# robotShield_Schematic.net
KiCad netlist of a schematic drawn in Altium Designer
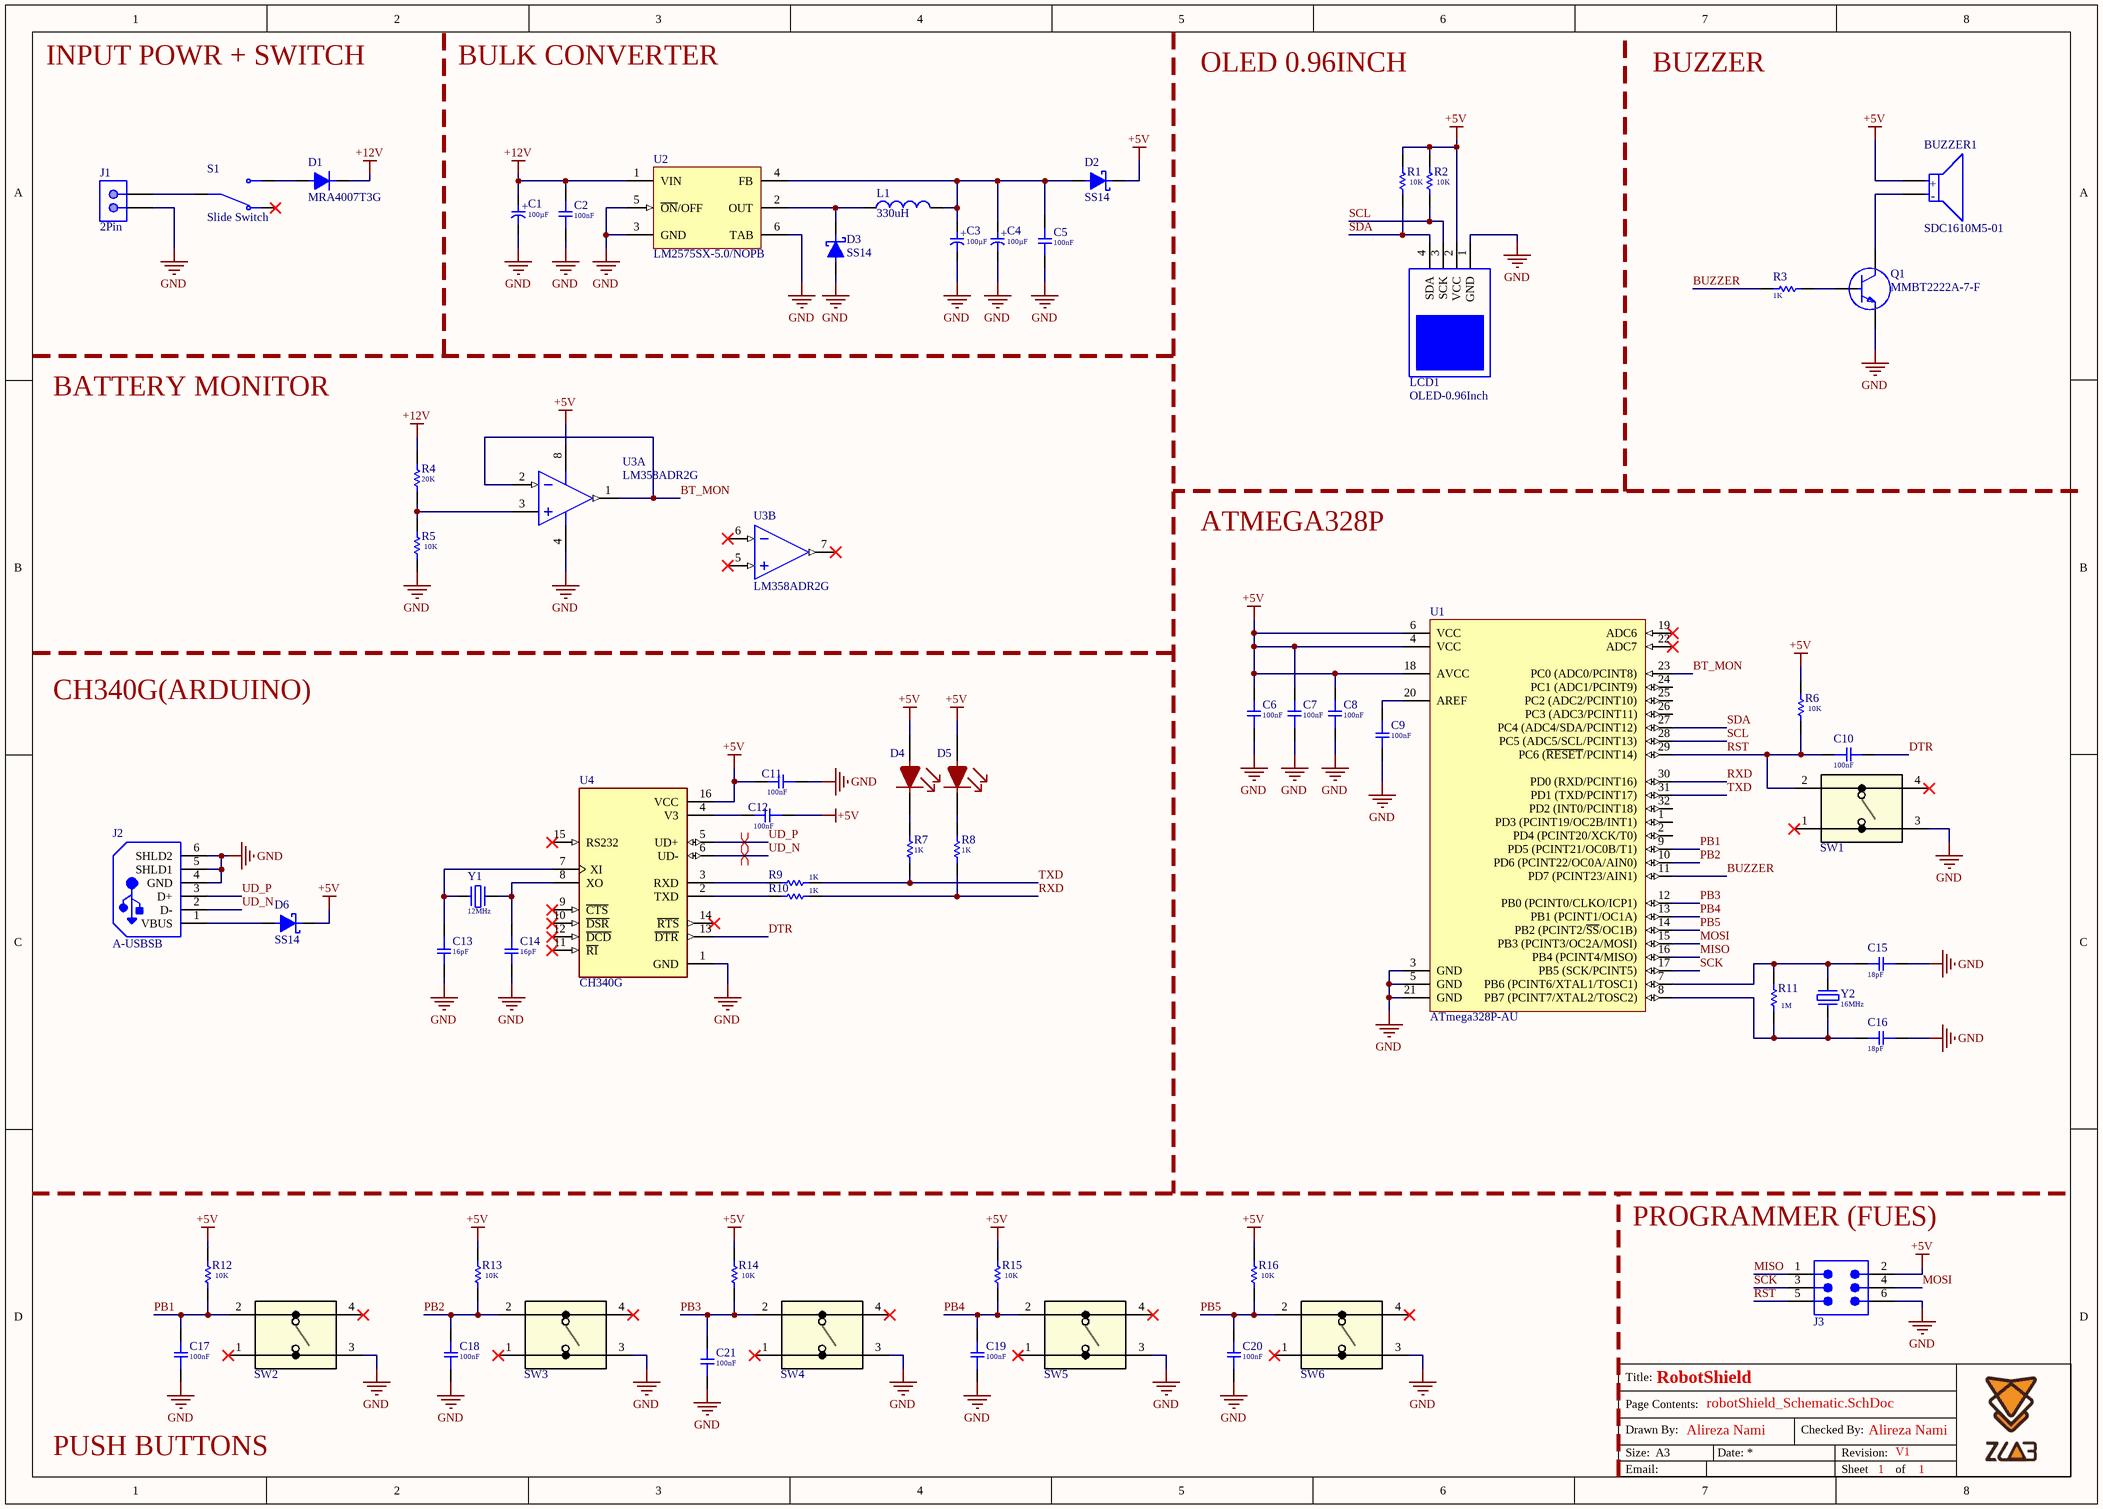
[diagram p0: robotShield_Schematic.SchDoc]

(export (version "E")
  (design (tool "Eeschema 10.0.6"))
  (components
    (comp (ref "BUZZER1")
      (value "SDC1610M5-01")
      (footprint "BUZZER")
      (description "AUDIO MAGNETIC INDICATOR 4-8V TH")
      (libsource (lib "robotShiedl") (part "BUZZER-5V"))
    )
    (comp (ref "C1")
      (value "MAL215376101E3")
      (footprint "CE-8x10mm")
      (description "MAL215376101E3 Cap Aluminum 100uF 25V 20% (8 X 10mm) SMD 0.5 Ohm 180mA 3000h 105C Blister T/R")
      (fields
        (field (name "VOLTAGE") "25V")
        (field (name "TOLERANCE") "20%")
        (field (name "CAPACITANCE") "100µF")
      )
      (libsource (lib "robotShiedl") (part "CE-100uF-25V"))
    )
    (comp (ref "C2")
      (value "CGA3E2X7R1H104K080AA")
      (footprint "C0603")
      (description "Cap Ceramic 100nF 50V X7R 10% Pad SMD 0603 +125°C Automotive T/R")
      (fields
        (field (name "TOLERANCE") "10%")
        (field (name "CAPACITANCE") "100nF")
        (field (name "VOLTAGE") "50V")
      )
      (libsource (lib "robotShiedl") (part "100N-50V-X7R-0603"))
    )
    (comp (ref "C3")
      (value "MAL215376101E3")
      (footprint "CE-8x10mm")
      (description "MAL215376101E3 Cap Aluminum 100uF 25V 20% (8 X 10mm) SMD 0.5 Ohm 180mA 3000h 105C Blister T/R")
      (fields
        (field (name "VOLTAGE") "25V")
        (field (name "TOLERANCE") "20%")
        (field (name "CAPACITANCE") "100µF")
      )
      (libsource (lib "robotShiedl") (part "CE-100uF-25V"))
    )
    (comp (ref "C4")
      (value "MAL215376101E3")
      (footprint "CE-8x10mm")
      (description "MAL215376101E3 Cap Aluminum 100uF 25V 20% (8 X 10mm) SMD 0.5 Ohm 180mA 3000h 105C Blister T/R")
      (fields
        (field (name "VOLTAGE") "25V")
        (field (name "TOLERANCE") "20%")
        (field (name "CAPACITANCE") "100µF")
      )
      (libsource (lib "robotShiedl") (part "CE-100uF-25V"))
    )
    (comp (ref "C5")
      (value "CGA3E2X7R1H104K080AA")
      (footprint "C0603")
      (description "Cap Ceramic 100nF 50V X7R 10% Pad SMD 0603 +125°C Automotive T/R")
      (fields
        (field (name "TOLERANCE") "10%")
        (field (name "CAPACITANCE") "100nF")
        (field (name "VOLTAGE") "50V")
      )
      (libsource (lib "robotShiedl") (part "100N-50V-X7R-0603"))
    )
    (comp (ref "C6")
      (value "CGA3E2X7R1H104K080AA")
      (footprint "C0603")
      (description "Cap Ceramic 100nF 50V X7R 10% Pad SMD 0603 +125°C Automotive T/R")
      (fields
        (field (name "TOLERANCE") "10%")
        (field (name "CAPACITANCE") "100nF")
        (field (name "VOLTAGE") "50V")
      )
      (libsource (lib "robotShiedl") (part "100N-50V-X7R-0603"))
    )
    (comp (ref "C7")
      (value "CGA3E2X7R1H104K080AA")
      (footprint "C0603")
      (description "Cap Ceramic 100nF 50V X7R 10% Pad SMD 0603 +125°C Automotive T/R")
      (fields
        (field (name "TOLERANCE") "10%")
        (field (name "CAPACITANCE") "100nF")
        (field (name "VOLTAGE") "50V")
      )
      (libsource (lib "robotShiedl") (part "100N-50V-X7R-0603"))
    )
    (comp (ref "C8")
      (value "CGA3E2X7R1H104K080AA")
      (footprint "C0603")
      (description "Cap Ceramic 100nF 50V X7R 10% Pad SMD 0603 +125°C Automotive T/R")
      (fields
        (field (name "TOLERANCE") "10%")
        (field (name "CAPACITANCE") "100nF")
        (field (name "VOLTAGE") "50V")
      )
      (libsource (lib "robotShiedl") (part "100N-50V-X7R-0603"))
    )
    (comp (ref "C9")
      (value "CGA3E2X7R1H104K080AA")
      (footprint "C0603")
      (description "Cap Ceramic 100nF 50V X7R 10% Pad SMD 0603 +125°C Automotive T/R")
      (fields
        (field (name "TOLERANCE") "10%")
        (field (name "CAPACITANCE") "100nF")
        (field (name "VOLTAGE") "50V")
      )
      (libsource (lib "robotShiedl") (part "100N-50V-X7R-0603"))
    )
    (comp (ref "C10")
      (value "CGA3E2X7R1H104K080AA")
      (footprint "C0603")
      (description "Cap Ceramic 100nF 50V X7R 10% Pad SMD 0603 +125°C Automotive T/R")
      (fields
        (field (name "TOLERANCE") "10%")
        (field (name "CAPACITANCE") "100nF")
        (field (name "VOLTAGE") "50V")
      )
      (libsource (lib "robotShiedl") (part "100N-50V-X7R-0603"))
    )
    (comp (ref "C11")
      (value "CGA3E2X7R1H104K080AA")
      (footprint "C0603")
      (description "Cap Ceramic 100nF 50V X7R 10% Pad SMD 0603 +125°C Automotive T/R")
      (fields
        (field (name "TOLERANCE") "10%")
        (field (name "CAPACITANCE") "100nF")
        (field (name "VOLTAGE") "50V")
      )
      (libsource (lib "robotShiedl") (part "100N-50V-X7R-0603"))
    )
    (comp (ref "C12")
      (value "CGA3E2X7R1H104K080AA")
      (footprint "C0603")
      (description "Cap Ceramic 100nF 50V X7R 10% Pad SMD 0603 +125°C Automotive T/R")
      (fields
        (field (name "TOLERANCE") "10%")
        (field (name "CAPACITANCE") "100nF")
        (field (name "VOLTAGE") "50V")
      )
      (libsource (lib "robotShiedl") (part "100N-50V-X7R-0603"))
    )
    (comp (ref "C13")
      (value "16pF")
      (footprint "C0603")
      (description "16 pF ±5% 25V Ceramic Capacitor C0G, NP0 0603 (1608 Metric)")
      (fields
        (field (name "MANUFACTURER") "KEMET")
        (field (name "MANUFACTURER PART NUMBER") "C0603C160J3GACTU")
      )
      (libsource (lib "robotShiedl") (part "16P-25V-C0G-0603"))
    )
    (comp (ref "C14")
      (value "16pF")
      (footprint "C0603")
      (description "16 pF ±5% 25V Ceramic Capacitor C0G, NP0 0603 (1608 Metric)")
      (fields
        (field (name "MANUFACTURER") "KEMET")
        (field (name "MANUFACTURER PART NUMBER") "C0603C160J3GACTU")
      )
      (libsource (lib "robotShiedl") (part "16P-25V-C0G-0603"))
    )
    (comp (ref "C15")
      (value "18pF")
      (footprint "C0603")
      (description "0603 (1608METRIC) Ceramic Capacitor SMD Comm C0G 25V 18PF ±5% C0G NP0")
      (fields
        (field (name "MANUFACTURER") "KEMET")
        (field (name "MANUFACTURER PART NUMBER") "C0603C180J3GACTU")
      )
      (libsource (lib "robotShiedl") (part "18P-25V-C0G-0603"))
    )
    (comp (ref "C16")
      (value "18pF")
      (footprint "C0603")
      (description "0603 (1608METRIC) Ceramic Capacitor SMD Comm C0G 25V 18PF ±5% C0G NP0")
      (fields
        (field (name "MANUFACTURER") "KEMET")
        (field (name "MANUFACTURER PART NUMBER") "C0603C180J3GACTU")
      )
      (libsource (lib "robotShiedl") (part "18P-25V-C0G-0603"))
    )
    (comp (ref "C17")
      (value "CGA3E2X7R1H104K080AA")
      (footprint "C0603")
      (description "Cap Ceramic 100nF 50V X7R 10% Pad SMD 0603 +125°C Automotive T/R")
      (fields
        (field (name "TOLERANCE") "10%")
        (field (name "CAPACITANCE") "100nF")
        (field (name "VOLTAGE") "50V")
      )
      (libsource (lib "robotShiedl") (part "100N-50V-X7R-0603"))
    )
    (comp (ref "C18")
      (value "CGA3E2X7R1H104K080AA")
      (footprint "C0603")
      (description "Cap Ceramic 100nF 50V X7R 10% Pad SMD 0603 +125°C Automotive T/R")
      (fields
        (field (name "TOLERANCE") "10%")
        (field (name "CAPACITANCE") "100nF")
        (field (name "VOLTAGE") "50V")
      )
      (libsource (lib "robotShiedl") (part "100N-50V-X7R-0603"))
    )
    (comp (ref "C19")
      (value "CGA3E2X7R1H104K080AA")
      (footprint "C0603")
      (description "Cap Ceramic 100nF 50V X7R 10% Pad SMD 0603 +125°C Automotive T/R")
      (fields
        (field (name "TOLERANCE") "10%")
        (field (name "CAPACITANCE") "100nF")
        (field (name "VOLTAGE") "50V")
      )
      (libsource (lib "robotShiedl") (part "100N-50V-X7R-0603"))
    )
    (comp (ref "C20")
      (value "CGA3E2X7R1H104K080AA")
      (footprint "C0603")
      (description "Cap Ceramic 100nF 50V X7R 10% Pad SMD 0603 +125°C Automotive T/R")
      (fields
        (field (name "TOLERANCE") "10%")
        (field (name "CAPACITANCE") "100nF")
        (field (name "VOLTAGE") "50V")
      )
      (libsource (lib "robotShiedl") (part "100N-50V-X7R-0603"))
    )
    (comp (ref "C21")
      (value "CGA3E2X7R1H104K080AA")
      (footprint "C0603")
      (description "Cap Ceramic 100nF 50V X7R 10% Pad SMD 0603 +125°C Automotive T/R")
      (fields
        (field (name "TOLERANCE") "10%")
        (field (name "CAPACITANCE") "100nF")
        (field (name "VOLTAGE") "50V")
      )
      (libsource (lib "robotShiedl") (part "100N-50V-X7R-0603"))
    )
    (comp (ref "D1")
      (value "MRA4007T3G")
      (footprint "SMA")
      (description "Surface Mount Standard Recovery Power Rectifier, 2-Pin SMA, Pb-Free, Tape and Reel")
      (fields (field (name "MANUFACTURER") "On Semiconductor"))
      (libsource (lib "robotShiedl") (part "M7"))
    )
    (comp (ref "D2")
      (value "SS14")
      (footprint "SMA")
      (description "DIODE SCHOTTKY 40V 1A DO214AC")
      (fields
        (field (name "OCTOPART") "https://octopart.com/ss14-e3%2F61t-vishay-39552847")
        (field (name "MANUFACTURER") "Vishay")
      )
      (libsource (lib "robotShiedl") (part "SS14"))
    )
    (comp (ref "D3")
      (value "SS14")
      (footprint "SMA")
      (description "DIODE SCHOTTKY 40V 1A DO214AC")
      (fields
        (field (name "OCTOPART") "https://octopart.com/ss14-e3%2F61t-vishay-39552847")
        (field (name "MANUFACTURER") "Vishay")
      )
      (libsource (lib "robotShiedl") (part "SS14"))
    )
    (comp (ref "D4")
      (value "SML-D12U1WT86")
      (footprint "LED_RED_0603")
      (description "LED RED DIFFUSED 1608 SMD")
      (fields
        (field (name "MANUFACTURER") "Rohm")
        (field (name "OCTOPART") "https://octopart.com/sml-d12u1wt86-rohm-70850259")
      )
      (libsource (lib "robotShiedl") (part "LED_RED_0603"))
    )
    (comp (ref "D5")
      (value "SML-D12U1WT86")
      (footprint "LED_RED_0603")
      (description "LED RED DIFFUSED 1608 SMD")
      (fields
        (field (name "MANUFACTURER") "Rohm")
        (field (name "OCTOPART") "https://octopart.com/sml-d12u1wt86-rohm-70850259")
      )
      (libsource (lib "robotShiedl") (part "LED_RED_0603"))
    )
    (comp (ref "D6")
      (value "SS14")
      (footprint "SMA")
      (description "DIODE SCHOTTKY 40V 1A DO214AC")
      (fields
        (field (name "OCTOPART") "https://octopart.com/ss14-e3%2F61t-vishay-39552847")
        (field (name "MANUFACTURER") "Vishay")
      )
      (libsource (lib "robotShiedl") (part "SS14"))
    )
    (comp (ref "J1")
      (value "2Pin")
      (footprint "MOLX-2P-2.54MM")
      (fields (field (name "PARTNUMBER") "22-23-2021"))
      (libsource (lib "robotShiedl") (part "Header_2P_2.54mm"))
    )
    (comp (ref "J2")
      (value "A-USBSB")
      (footprint "USBS-B")
      (description "Connector Receptacle, USB Type B, Right Angle, -20 to 85 degC, 4-Pin THD, RoHS, Tray")
      (fields (field (name "MANUFACTURER") "ASSMANN WSW"))
      (libsource (lib "robotShiedl") (part "A-USBSB"))
    )
    (comp (ref "J3")
      (value "61200621621")
      (footprint "ICSP")
      (description "CONN HEADER VERT 6POS 2.54MM")
      (libsource (lib "robotShiedl") (part "ICSP"))
    )
    (comp (ref "L1")
      (value "330uH")
      (footprint "WE-PD_7332R")
      (description "Inductor Power Shielded Wirewound 330uH 20% 1KHz Ferrite 0.34A 1.5Ohm DCR Automotive T/R")
      (fields
        (field (name "MANUFACTURER") "Bourns")
        (field (name "MANUFACTURER PART NUMBER") "SRR0745A-331M")
      )
      (libsource (lib "robotShiedl") (part "330uH-0.34A"))
    )
    (comp (ref "LCD1")
      (value "OLED-0.96Inch")
      (footprint "OLED")
      (description "Monochrome 0.96 128x64 OLED graphic display ¦ Adafruit Industries 326")
      (fields
        (field (name "MANUFACTURER") "Adafruit Industries")
        (field (name "MANUFACTURER PART NUMBER") "326")
      )
      (libsource (lib "robotShiedl") (part "OLED-0.96Inch"))
    )
    (comp (ref "Q1")
      (value "MMBT2222A-7-F")
      (footprint "SOT23")
      (description "TRANS NPN 40V 0.6A SMD SOT23-3")
      (fields (field (name "VOLTAGE") "40V"))
      (libsource (lib "robotShiedl") (part "MMBT2222A"))
    )
    (comp (ref "R1")
      (value "10K")
      (footprint "R0603")
      (description "100Mw Thick Film Resistors 100Ppm/ 5% 10K 0603 Chip Resistor Surface Mount Rohs")
      (fields
        (field (name "MANUFACTURER") "Yageo")
        (field (name "MANUFACTURER PART NUMBER") "RC0603JR-0710KL")
      )
      (libsource (lib "robotShiedl") (part "10K-5%-0603"))
    )
    (comp (ref "R2")
      (value "10K")
      (footprint "R0603")
      (description "100Mw Thick Film Resistors 100Ppm/ 5% 10K 0603 Chip Resistor Surface Mount Rohs")
      (fields
        (field (name "MANUFACTURER") "Yageo")
        (field (name "MANUFACTURER PART NUMBER") "RC0603JR-0710KL")
      )
      (libsource (lib "robotShiedl") (part "10K-5%-0603"))
    )
    (comp (ref "R3")
      (value "RC0603JR-071KL")
      (footprint "R0603")
      (description "Chip Resistor, 1 KOhm, +/- 5%, 0.063 W, -55 to 155 degC, 0603 (1608 Metric), RoHS, Tape and Reel")
      (fields (field (name "RESISTANCE") "1K") (field (name "MANUFACTURER") "Yageo"))
      (libsource (lib "robotShiedl") (part "1K-5%-0603"))
    )
    (comp (ref "R4")
      (value "20K")
      (footprint "R0603")
      (description "Res Thick Film 0603 20K Ohm 5% 0.1W(1/10W) ±100ppm/C Pad SMD T/R")
      (fields
        (field (name "MANUFACTURER") "Yageo")
        (field (name "MANUFACTURER PART NUMBER") "RC0603JR-0720KL")
      )
      (libsource (lib "robotShiedl") (part "20K-5%-0603"))
    )
    (comp (ref "R5")
      (value "10K")
      (footprint "R0603")
      (description "100Mw Thick Film Resistors 100Ppm/ 5% 10K 0603 Chip Resistor Surface Mount Rohs")
      (fields
        (field (name "MANUFACTURER") "Yageo")
        (field (name "MANUFACTURER PART NUMBER") "RC0603JR-0710KL")
      )
      (libsource (lib "robotShiedl") (part "10K-5%-0603"))
    )
    (comp (ref "R6")
      (value "10K")
      (footprint "R0603")
      (description "100Mw Thick Film Resistors 100Ppm/ 5% 10K 0603 Chip Resistor Surface Mount Rohs")
      (fields
        (field (name "MANUFACTURER") "Yageo")
        (field (name "MANUFACTURER PART NUMBER") "RC0603JR-0710KL")
      )
      (libsource (lib "robotShiedl") (part "10K-5%-0603"))
    )
    (comp (ref "R7")
      (value "RC0603JR-071KL")
      (footprint "R0603")
      (description "Chip Resistor, 1 KOhm, +/- 5%, 0.063 W, -55 to 155 degC, 0603 (1608 Metric), RoHS, Tape and Reel")
      (fields (field (name "RESISTANCE") "1K") (field (name "MANUFACTURER") "Yageo"))
      (libsource (lib "robotShiedl") (part "1K-5%-0603"))
    )
    (comp (ref "R8")
      (value "RC0603JR-071KL")
      (footprint "R0603")
      (description "Chip Resistor, 1 KOhm, +/- 5%, 0.063 W, -55 to 155 degC, 0603 (1608 Metric), RoHS, Tape and Reel")
      (fields (field (name "RESISTANCE") "1K") (field (name "MANUFACTURER") "Yageo"))
      (libsource (lib "robotShiedl") (part "1K-5%-0603"))
    )
    (comp (ref "R9")
      (value "RC0603JR-071KL")
      (footprint "R0603")
      (description "Chip Resistor, 1 KOhm, +/- 5%, 0.063 W, -55 to 155 degC, 0603 (1608 Metric), RoHS, Tape and Reel")
      (fields (field (name "RESISTANCE") "1K") (field (name "MANUFACTURER") "Yageo"))
      (libsource (lib "robotShiedl") (part "1K-5%-0603"))
    )
    (comp (ref "R10")
      (value "RC0603JR-071KL")
      (footprint "R0603")
      (description "Chip Resistor, 1 KOhm, +/- 5%, 0.063 W, -55 to 155 degC, 0603 (1608 Metric), RoHS, Tape and Reel")
      (fields (field (name "RESISTANCE") "1K") (field (name "MANUFACTURER") "Yageo"))
      (libsource (lib "robotShiedl") (part "1K-5%-0603"))
    )
    (comp (ref "R11")
      (value "1M")
      (footprint "R0603")
      (description "100Mw Thick Film Resistors 100Ppm/ 5% 1M 0603 Chip Resistor Surface Mount Rohs")
      (fields
        (field (name "MANUFACTURER") "Yageo")
        (field (name "MANUFACTURER PART NUMBER") "RC0603JR-071ML")
      )
      (libsource (lib "robotShiedl") (part "1M-5%-0603"))
    )
    (comp (ref "R12")
      (value "10K")
      (footprint "R0603")
      (description "100Mw Thick Film Resistors 100Ppm/ 5% 10K 0603 Chip Resistor Surface Mount Rohs")
      (fields
        (field (name "MANUFACTURER") "Yageo")
        (field (name "MANUFACTURER PART NUMBER") "RC0603JR-0710KL")
      )
      (libsource (lib "robotShiedl") (part "10K-5%-0603"))
    )
    (comp (ref "R13")
      (value "10K")
      (footprint "R0603")
      (description "100Mw Thick Film Resistors 100Ppm/ 5% 10K 0603 Chip Resistor Surface Mount Rohs")
      (fields
        (field (name "MANUFACTURER") "Yageo")
        (field (name "MANUFACTURER PART NUMBER") "RC0603JR-0710KL")
      )
      (libsource (lib "robotShiedl") (part "10K-5%-0603"))
    )
    (comp (ref "R14")
      (value "10K")
      (footprint "R0603")
      (description "100Mw Thick Film Resistors 100Ppm/ 5% 10K 0603 Chip Resistor Surface Mount Rohs")
      (fields
        (field (name "MANUFACTURER") "Yageo")
        (field (name "MANUFACTURER PART NUMBER") "RC0603JR-0710KL")
      )
      (libsource (lib "robotShiedl") (part "10K-5%-0603"))
    )
    (comp (ref "R15")
      (value "10K")
      (footprint "R0603")
      (description "100Mw Thick Film Resistors 100Ppm/ 5% 10K 0603 Chip Resistor Surface Mount Rohs")
      (fields
        (field (name "MANUFACTURER") "Yageo")
        (field (name "MANUFACTURER PART NUMBER") "RC0603JR-0710KL")
      )
      (libsource (lib "robotShiedl") (part "10K-5%-0603"))
    )
    (comp (ref "R16")
      (value "10K")
      (footprint "R0603")
      (description "100Mw Thick Film Resistors 100Ppm/ 5% 10K 0603 Chip Resistor Surface Mount Rohs")
      (fields
        (field (name "MANUFACTURER") "Yageo")
        (field (name "MANUFACTURER PART NUMBER") "RC0603JR-0710KL")
      )
      (libsource (lib "robotShiedl") (part "10K-5%-0603"))
    )
    (comp (ref "S1")
      (value "Slide Switch")
      (footprint "SLIDE_SWITCH_RIGHT")
      (description "Slide Switch SPDT Through Hole, Right Angle")
      (fields (field (name "MF") "TE Connectivity") (field (name "MP") "STS121RA04"))
      (libsource (lib "robotShiedl") (part "SPDT"))
    )
    (comp (ref "SW1")
      (value "222AMVBAR")
      (footprint "TS_6x6x5")
      (description "SWITCH TACTILE SPST-NO 0.05A 12V")
      (fields (field (name "COPYRIGHT") "Copyright (C) 2025 Ultra Librarian. All rights reserved."))
      (libsource (lib "robotShiedl") (part "TactileSwitch_6x6x5"))
    )
    (comp (ref "SW2")
      (value "222AMVBAR")
      (footprint "TS_6x6x5")
      (description "SWITCH TACTILE SPST-NO 0.05A 12V")
      (fields (field (name "COPYRIGHT") "Copyright (C) 2025 Ultra Librarian. All rights reserved."))
      (libsource (lib "robotShiedl") (part "TactileSwitch_6x6x5"))
    )
    (comp (ref "SW3")
      (value "222AMVBAR")
      (footprint "TS_6x6x5")
      (description "SWITCH TACTILE SPST-NO 0.05A 12V")
      (fields (field (name "COPYRIGHT") "Copyright (C) 2025 Ultra Librarian. All rights reserved."))
      (libsource (lib "robotShiedl") (part "TactileSwitch_6x6x5"))
    )
    (comp (ref "SW4")
      (value "222AMVBAR")
      (footprint "TS_6x6x5")
      (description "SWITCH TACTILE SPST-NO 0.05A 12V")
      (fields (field (name "COPYRIGHT") "Copyright (C) 2025 Ultra Librarian. All rights reserved."))
      (libsource (lib "robotShiedl") (part "TactileSwitch_6x6x5"))
    )
    (comp (ref "SW5")
      (value "222AMVBAR")
      (footprint "TS_6x6x5")
      (description "SWITCH TACTILE SPST-NO 0.05A 12V")
      (fields (field (name "COPYRIGHT") "Copyright (C) 2025 Ultra Librarian. All rights reserved."))
      (libsource (lib "robotShiedl") (part "TactileSwitch_6x6x5"))
    )
    (comp (ref "SW6")
      (value "222AMVBAR")
      (footprint "TS_6x6x5")
      (description "SWITCH TACTILE SPST-NO 0.05A 12V")
      (fields (field (name "COPYRIGHT") "Copyright (C) 2025 Ultra Librarian. All rights reserved."))
      (libsource (lib "robotShiedl") (part "TactileSwitch_6x6x5"))
    )
    (comp (ref "U1")
      (value "ATmega328P-AU")
      (footprint "TQFP32")
      (libsource (lib "robotShiedl") (part "ATmega328P-AU"))
    )
    (comp (ref "U2")
      (value "LM2575SX-5.0/NOPB")
      (footprint "DPAK-5")
      (description "SIMPLE SWITCHER® 1A Step-Down Voltage Regulator, 5-pin TO-263, Pb-Free")
      (fields (field (name "MANUFACTURER") "Texas Instruments"))
      (libsource (lib "robotShiedl") (part "LM2575-5.0V"))
    )
    (comp (ref "U3")
      (value "LM358ADR2G")
      (footprint "SOIC-8")
      (fields (field (name "MANUFACTURER") "On Semiconductor"))
      (libsource (lib "robotShiedl") (part "LM358"))
    )
    (comp (ref "U4")
      (value "CH340G")
      (footprint "SOIC-16")
      (description "USB Interface Integrated Circuit")
      (fields (field (name "MP") "Ch340G") (field (name "MF") "WCH"))
      (libsource (lib "robotShiedl") (part "CH340G"))
    )
    (comp (ref "Y1")
      (value "LFXTAL003210BULK")
      (footprint "XTAL-SMD")
      (description "CRYSTAL 12.0MHZ 16PF SMD")
      (fields
        (field (name "MANUFACTURER") "IQD Frequency Products")
        (field (name "OCTOPART") "https://octopart.com/lfxtal003210bulk-iqd+frequency+products-20904063")
        (field (name "FREQUENCY") "12MHz")
      )
      (libsource (lib "robotShiedl") (part "CRYSTAL-12MHZ"))
    )
    (comp (ref "Y2")
      (value "ABLS-16.000MHZ-K4T")
      (footprint "XTAL-SMD")
      (description "CRYSTAL 16.0000MHZ 18PF SMD")
      (fields
        (field (name "TOLERANCE") "30ppm")
        (field (name "OCTOPART") "https://octopart.com/abls-16.000mhz-k4t-abracon-18618626")
        (field (name "FREQUENCY") "16MHz")
      )
      (libsource (lib "robotShiedl") (part "CRYSTAL-16MHZ"))
    )
  )
  (nets
    (net (code "1") (name "+5V") (class "Default")
      (node (ref "BUZZER1") (pin "2") (pinfunction "A_2") (pintype "passive"))
      (node (ref "C11") (pin "1") (pinfunction "1_1") (pintype "passive"))
      (node (ref "C12") (pin "2") (pinfunction "2_2") (pintype "passive"))
      (node (ref "C6") (pin "1") (pinfunction "1_1") (pintype "passive"))
      (node (ref "C7") (pin "1") (pinfunction "1_1") (pintype "passive"))
      (node (ref "C8") (pin "1") (pinfunction "1_1") (pintype "passive"))
      (node (ref "D2") (pin "1") (pinfunction "C_1") (pintype "passive"))
      (node (ref "D4") (pin "2") (pinfunction "A_2") (pintype "passive"))
      (node (ref "D5") (pin "2") (pinfunction "A_2") (pintype "passive"))
      (node (ref "D6") (pin "1") (pinfunction "C_1") (pintype "passive"))
      (node (ref "J3") (pin "2") (pinfunction "2_2") (pintype "passive"))
      (node (ref "LCD1") (pin "2") (pinfunction "VCC_2") (pintype "passive"))
      (node (ref "R1") (pin "2") (pinfunction "2_2") (pintype "passive"))
      (node (ref "R12") (pin "2") (pinfunction "2_2") (pintype "passive"))
      (node (ref "R13") (pin "2") (pinfunction "2_2") (pintype "passive"))
      (node (ref "R14") (pin "2") (pinfunction "2_2") (pintype "passive"))
      (node (ref "R15") (pin "2") (pinfunction "2_2") (pintype "passive"))
      (node (ref "R16") (pin "2") (pinfunction "2_2") (pintype "passive"))
      (node (ref "R2") (pin "2") (pinfunction "2_2") (pintype "passive"))
      (node (ref "R6") (pin "2") (pinfunction "2_2") (pintype "passive"))
      (node (ref "U1") (pin "18") (pinfunction "AVCC_18") (pintype "power_in"))
      (node (ref "U1") (pin "4") (pinfunction "VCC_4") (pintype "power_in"))
      (node (ref "U1") (pin "6") (pinfunction "VCC_6") (pintype "power_in"))
      (node (ref "U3") (pin "8") (pinfunction "8_8") (pintype "passive"))
      (node (ref "U4") (pin "16") (pinfunction "VCC_16") (pintype "power_in"))
    )
    (net (code "2") (name "+12V") (class "Default")
      (node (ref "C1") (pin "2") (pinfunction "A_2") (pintype "passive"))
      (node (ref "C2") (pin "1") (pinfunction "1_1") (pintype "passive"))
      (node (ref "D1") (pin "1") (pinfunction "K_1") (pintype "passive"))
      (node (ref "R4") (pin "2") (pinfunction "2_2") (pintype "passive"))
      (node (ref "U2") (pin "1") (pinfunction "VIN_1") (pintype "power_in"))
    )
    (net (code "3") (name "/BT_MON") (class "Default")
      (node (ref "U1") (pin "23") (pinfunction "PC0_(ADC0/PCINT8)_23") (pintype "input"))
      (node (ref "U3") (pin "1") (pinfunction "OUTA_1") (pintype "output"))
      (node (ref "U3") (pin "2") (pinfunction "INA-_2") (pintype "input"))
    )
    (net (code "4") (name "/BUZZER") (class "Default")
      (node (ref "R3") (pin "2") (pinfunction "2_2") (pintype "passive"))
      (node (ref "U1") (pin "11") (pinfunction "PD7_(PCINT23/AIN1)_11") (pintype "bidirectional"))
    )
    (net (code "5") (name "/DTR") (class "Default")
      (node (ref "C10") (pin "1") (pinfunction "1_1") (pintype "passive"))
      (node (ref "U4") (pin "13") (pinfunction "~{DTR}_13") (pintype "output"))
    )
    (net (code "6") (name "/MISO") (class "Default")
      (node (ref "J3") (pin "1") (pinfunction "1_1") (pintype "passive"))
      (node (ref "U1") (pin "16") (pinfunction "PB4_(PCINT4/MISO)_16") (pintype "bidirectional"))
    )
    (net (code "7") (name "/MOSI") (class "Default")
      (node (ref "J3") (pin "4") (pinfunction "4_4") (pintype "passive"))
      (node (ref "U1") (pin "15") (pinfunction "PB3_(PCINT3/OC2A/MOSI)_15") (pintype "bidirectional"))
    )
    (net (code "8") (name "/PB1") (class "Default")
      (node (ref "C17") (pin "1") (pinfunction "1_1") (pintype "passive"))
      (node (ref "R12") (pin "1") (pinfunction "1_1") (pintype "passive"))
      (node (ref "SW2") (pin "2") (pinfunction "2_2") (pintype "passive"))
      (node (ref "U1") (pin "9") (pinfunction "PD5_(PCINT21/OC0B/T1)_9") (pintype "bidirectional"))
    )
    (net (code "9") (name "/PB2") (class "Default")
      (node (ref "C18") (pin "1") (pinfunction "1_1") (pintype "passive"))
      (node (ref "R13") (pin "1") (pinfunction "1_1") (pintype "passive"))
      (node (ref "SW3") (pin "2") (pinfunction "2_2") (pintype "passive"))
      (node (ref "U1") (pin "10") (pinfunction "PD6_(PCINT22/OC0A/AIN0)_10") (pintype "bidirectional"))
    )
    (net (code "10") (name "/PB3") (class "Default")
      (node (ref "C21") (pin "1") (pinfunction "1_1") (pintype "passive"))
      (node (ref "R14") (pin "1") (pinfunction "1_1") (pintype "passive"))
      (node (ref "SW4") (pin "2") (pinfunction "2_2") (pintype "passive"))
      (node (ref "U1") (pin "12") (pinfunction "PB0_(PCINT0/CLKO/ICP1)_12") (pintype "bidirectional"))
    )
    (net (code "11") (name "/PB4") (class "Default")
      (node (ref "C19") (pin "1") (pinfunction "1_1") (pintype "passive"))
      (node (ref "R15") (pin "1") (pinfunction "1_1") (pintype "passive"))
      (node (ref "SW5") (pin "2") (pinfunction "2_2") (pintype "passive"))
      (node (ref "U1") (pin "13") (pinfunction "PB1_(PCINT1/OC1A)_13") (pintype "bidirectional"))
    )
    (net (code "12") (name "/PB5") (class "Default")
      (node (ref "C20") (pin "1") (pinfunction "1_1") (pintype "passive"))
      (node (ref "R16") (pin "1") (pinfunction "1_1") (pintype "passive"))
      (node (ref "SW6") (pin "2") (pinfunction "2_2") (pintype "passive"))
      (node (ref "U1") (pin "14") (pinfunction "PB2_(PCINT2/~{SS}/OC1B)_14") (pintype "bidirectional"))
    )
    (net (code "13") (name "/RST") (class "Default")
      (node (ref "C10") (pin "2") (pinfunction "2_2") (pintype "passive"))
      (node (ref "J3") (pin "5") (pinfunction "5_5") (pintype "passive"))
      (node (ref "R6") (pin "1") (pinfunction "1_1") (pintype "passive"))
      (node (ref "SW1") (pin "2") (pinfunction "2_2") (pintype "passive"))
      (node (ref "U1") (pin "29") (pinfunction "PC6_(~{RESET}/PCINT14)_29") (pintype "bidirectional"))
    )
    (net (code "14") (name "/RXD") (class "Default")
      (node (ref "R10") (pin "2") (pinfunction "2_2") (pintype "passive"))
      (node (ref "R8") (pin "1") (pinfunction "1_1") (pintype "passive"))
      (node (ref "U1") (pin "30") (pinfunction "PD0_(RXD/PCINT16)_30") (pintype "bidirectional"))
    )
    (net (code "15") (name "/SCK") (class "Default")
      (node (ref "J3") (pin "3") (pinfunction "3_3") (pintype "passive"))
      (node (ref "U1") (pin "17") (pinfunction "PB5_(SCK/PCINT5)_17") (pintype "bidirectional"))
    )
    (net (code "16") (name "/SCL") (class "Default")
      (node (ref "LCD1") (pin "3") (pinfunction "SCK_3") (pintype "passive"))
      (node (ref "R2") (pin "1") (pinfunction "1_1") (pintype "passive"))
      (node (ref "U1") (pin "28") (pinfunction "PC5_(ADC5/SCL/PCINT13)_28") (pintype "bidirectional"))
    )
    (net (code "17") (name "/SDA") (class "Default")
      (node (ref "LCD1") (pin "4") (pinfunction "SDA_4") (pintype "passive"))
      (node (ref "R1") (pin "1") (pinfunction "1_1") (pintype "passive"))
      (node (ref "U1") (pin "27") (pinfunction "PC4_(ADC4/SDA/PCINT12)_27") (pintype "bidirectional"))
    )
    (net (code "18") (name "/TXD") (class "Default")
      (node (ref "R7") (pin "1") (pinfunction "1_1") (pintype "passive"))
      (node (ref "R9") (pin "2") (pinfunction "2_2") (pintype "passive"))
      (node (ref "U1") (pin "31") (pinfunction "PD1_(TXD/PCINT17)_31") (pintype "bidirectional"))
    )
    (net (code "19") (name "/UD_N") (class "Default")
      (node (ref "J2") (pin "2") (pinfunction "D-_2") (pintype "passive"))
      (node (ref "U4") (pin "6") (pinfunction "UD-_6") (pintype "bidirectional"))
    )
    (net (code "20") (name "/UD_P") (class "Default")
      (node (ref "J2") (pin "3") (pinfunction "D+_3") (pintype "passive"))
      (node (ref "U4") (pin "5") (pinfunction "UD+_5") (pintype "bidirectional"))
    )
    (net (code "21") (name "GND") (class "Default")
      (node (ref "C1") (pin "1") (pinfunction "C_1") (pintype "passive"))
      (node (ref "C11") (pin "2") (pinfunction "2_2") (pintype "passive"))
      (node (ref "C13") (pin "1") (pinfunction "1_1") (pintype "passive"))
      (node (ref "C14") (pin "1") (pinfunction "1_1") (pintype "passive"))
      (node (ref "C15") (pin "2") (pinfunction "2_2") (pintype "passive"))
      (node (ref "C16") (pin "2") (pinfunction "2_2") (pintype "passive"))
      (node (ref "C17") (pin "2") (pinfunction "2_2") (pintype "passive"))
      (node (ref "C18") (pin "2") (pinfunction "2_2") (pintype "passive"))
      (node (ref "C19") (pin "2") (pinfunction "2_2") (pintype "passive"))
      (node (ref "C2") (pin "2") (pinfunction "2_2") (pintype "passive"))
      (node (ref "C20") (pin "2") (pinfunction "2_2") (pintype "passive"))
      (node (ref "C21") (pin "2") (pinfunction "2_2") (pintype "passive"))
      (node (ref "C3") (pin "1") (pinfunction "C_1") (pintype "passive"))
      (node (ref "C4") (pin "1") (pinfunction "C_1") (pintype "passive"))
      (node (ref "C5") (pin "2") (pinfunction "2_2") (pintype "passive"))
      (node (ref "C6") (pin "2") (pinfunction "2_2") (pintype "passive"))
      (node (ref "C7") (pin "2") (pinfunction "2_2") (pintype "passive"))
      (node (ref "C8") (pin "2") (pinfunction "2_2") (pintype "passive"))
      (node (ref "C9") (pin "1") (pinfunction "1_1") (pintype "passive"))
      (node (ref "D3") (pin "2") (pinfunction "A_2") (pintype "passive"))
      (node (ref "J1") (pin "1") (pinfunction "1_1") (pintype "passive"))
      (node (ref "J2") (pin "4") (pinfunction "GND_4") (pintype "passive"))
      (node (ref "J2") (pin "5") (pinfunction "SHLD1_5") (pintype "passive"))
      (node (ref "J2") (pin "6") (pinfunction "SHLD2_6") (pintype "passive"))
      (node (ref "J3") (pin "6") (pinfunction "6_6") (pintype "passive"))
      (node (ref "LCD1") (pin "1") (pinfunction "GND_1") (pintype "passive"))
      (node (ref "Q1") (pin "2") (pinfunction "E_2") (pintype "passive"))
      (node (ref "R5") (pin "1") (pinfunction "1_1") (pintype "passive"))
      (node (ref "SW1") (pin "3") (pinfunction "3_3") (pintype "passive"))
      (node (ref "SW2") (pin "3") (pinfunction "3_3") (pintype "passive"))
      (node (ref "SW3") (pin "3") (pinfunction "3_3") (pintype "passive"))
      (node (ref "SW4") (pin "3") (pinfunction "3_3") (pintype "passive"))
      (node (ref "SW5") (pin "3") (pinfunction "3_3") (pintype "passive"))
      (node (ref "SW6") (pin "3") (pinfunction "3_3") (pintype "passive"))
      (node (ref "U1") (pin "21") (pinfunction "GND_21") (pintype "power_in"))
      (node (ref "U1") (pin "3") (pinfunction "GND_3") (pintype "power_in"))
      (node (ref "U1") (pin "5") (pinfunction "GND_5") (pintype "power_in"))
      (node (ref "U2") (pin "3") (pinfunction "GND_3") (pintype "power_in"))
      (node (ref "U2") (pin "5") (pinfunction "~{ON}/OFF_5") (pintype "input"))
      (node (ref "U2") (pin "6") (pinfunction "TAB_6") (pintype "power_in"))
      (node (ref "U3") (pin "4") (pinfunction "4_4") (pintype "passive"))
      (node (ref "U4") (pin "1") (pinfunction "GND_1") (pintype "power_in"))
    )
    (net (code "22") (name "Net-(BUZZER1-C)") (class "Default")
      (node (ref "BUZZER1") (pin "1") (pinfunction "C_1") (pintype "passive"))
      (node (ref "Q1") (pin "3") (pinfunction "C_3") (pintype "passive"))
    )
    (net (code "23") (name "Net-(C3-A)") (class "Default")
      (node (ref "C3") (pin "2") (pinfunction "A_2") (pintype "passive"))
      (node (ref "C4") (pin "2") (pinfunction "A_2") (pintype "passive"))
      (node (ref "C5") (pin "1") (pinfunction "1_1") (pintype "passive"))
      (node (ref "D2") (pin "2") (pinfunction "A_2") (pintype "passive"))
      (node (ref "L1") (pin "2") (pinfunction "2_2") (pintype "passive"))
      (node (ref "U2") (pin "4") (pinfunction "FB_4") (pintype "passive"))
    )
    (net (code "24") (name "Net-(D1-A)") (class "Default")
      (node (ref "D1") (pin "2") (pinfunction "A_2") (pintype "passive"))
      (node (ref "S1") (pin "3") (pinfunction "3_3") (pintype "passive"))
    )
    (net (code "25") (name "Net-(D3-C)") (class "Default")
      (node (ref "D3") (pin "1") (pinfunction "C_1") (pintype "passive"))
      (node (ref "L1") (pin "1") (pinfunction "1_1") (pintype "passive"))
      (node (ref "U2") (pin "2") (pinfunction "OUT_2") (pintype "power_in"))
    )
    (net (code "26") (name "Net-(D4-C)") (class "Default")
      (node (ref "D4") (pin "1") (pinfunction "C_1") (pintype "passive"))
      (node (ref "R7") (pin "2") (pinfunction "2_2") (pintype "passive"))
    )
    (net (code "27") (name "Net-(D5-C)") (class "Default")
      (node (ref "D5") (pin "1") (pinfunction "C_1") (pintype "passive"))
      (node (ref "R8") (pin "2") (pinfunction "2_2") (pintype "passive"))
    )
    (net (code "28") (name "Net-(D6-A)") (class "Default")
      (node (ref "D6") (pin "2") (pinfunction "A_2") (pintype "passive"))
      (node (ref "J2") (pin "1") (pinfunction "VBUS_1") (pintype "passive"))
    )
    (net (code "29") (name "Net-(J1-Pad2)") (class "Default")
      (node (ref "J1") (pin "2") (pinfunction "2_2") (pintype "passive"))
      (node (ref "S1") (pin "2") (pinfunction "2_2") (pintype "passive"))
    )
    (net (code "30") (name "Net-(Q1-B)") (class "Default")
      (node (ref "Q1") (pin "1") (pinfunction "B_1") (pintype "passive"))
      (node (ref "R3") (pin "1") (pinfunction "1_1") (pintype "passive"))
    )
    (net (code "31") (name "Net-(U1-AREF)") (class "Default")
      (node (ref "C9") (pin "2") (pinfunction "2_2") (pintype "passive"))
      (node (ref "U1") (pin "20") (pinfunction "AREF_20") (pintype "passive"))
    )
    (net (code "32") (name "Net-(U1-PB6_(PCINT6{slash}XTAL1{slash}TOSC1))") (class "Default")
      (node (ref "C15") (pin "1") (pinfunction "1_1") (pintype "passive"))
      (node (ref "R11") (pin "2") (pinfunction "2_2") (pintype "passive"))
      (node (ref "U1") (pin "7") (pinfunction "PB6_(PCINT6/XTAL1/TOSC1)_7") (pintype "bidirectional"))
      (node (ref "Y2") (pin "2") (pinfunction "2_2") (pintype "passive"))
    )
    (net (code "33") (name "Net-(U1-PB7_(PCINT7{slash}XTAL2{slash}TOSC2))") (class "Default")
      (node (ref "C16") (pin "1") (pinfunction "1_1") (pintype "passive"))
      (node (ref "R11") (pin "1") (pinfunction "1_1") (pintype "passive"))
      (node (ref "U1") (pin "8") (pinfunction "PB7_(PCINT7/XTAL2/TOSC2)_8") (pintype "bidirectional"))
      (node (ref "Y2") (pin "1") (pinfunction "1_1") (pintype "passive"))
    )
    (net (code "34") (name "Net-(U3A-INA+)") (class "Default")
      (node (ref "R4") (pin "1") (pinfunction "1_1") (pintype "passive"))
      (node (ref "R5") (pin "2") (pinfunction "2_2") (pintype "passive"))
      (node (ref "U3") (pin "3") (pinfunction "INA+_3") (pintype "passive"))
    )
    (net (code "35") (name "Net-(U4-RXD)") (class "Default")
      (node (ref "R9") (pin "1") (pinfunction "1_1") (pintype "passive"))
      (node (ref "U4") (pin "3") (pinfunction "RXD_3") (pintype "passive"))
    )
    (net (code "36") (name "Net-(U4-TXD)") (class "Default")
      (node (ref "R10") (pin "1") (pinfunction "1_1") (pintype "passive"))
      (node (ref "U4") (pin "2") (pinfunction "TXD_2") (pintype "passive"))
    )
    (net (code "37") (name "Net-(U4-V3)") (class "Default")
      (node (ref "C12") (pin "1") (pinfunction "1_1") (pintype "passive"))
      (node (ref "U4") (pin "4") (pinfunction "V3_4") (pintype "power_in"))
    )
    (net (code "38") (name "Net-(U4-XI)") (class "Default")
      (node (ref "C13") (pin "2") (pinfunction "2_2") (pintype "passive"))
      (node (ref "U4") (pin "7") (pinfunction "XI_7") (pintype "passive"))
      (node (ref "Y1") (pin "1") (pinfunction "1_1") (pintype "passive"))
    )
    (net (code "39") (name "Net-(U4-XO)") (class "Default")
      (node (ref "C14") (pin "2") (pinfunction "2_2") (pintype "passive"))
      (node (ref "U4") (pin "8") (pinfunction "XO_8") (pintype "passive"))
      (node (ref "Y1") (pin "2") (pinfunction "2_2") (pintype "passive"))
    )
    (net (code "40") (name "unconnected-(S1-Pad1)") (class "Default")
      (node (ref "S1") (pin "1") (pinfunction "1_1") (pintype "passive+no_connect"))
    )
    (net (code "41") (name "unconnected-(SW1-Pad1)") (class "Default")
      (node (ref "SW1") (pin "1") (pinfunction "1_1") (pintype "passive+no_connect"))
    )
    (net (code "42") (name "unconnected-(SW1-Pad4)") (class "Default")
      (node (ref "SW1") (pin "4") (pinfunction "4_4") (pintype "passive+no_connect"))
    )
    (net (code "43") (name "unconnected-(SW2-Pad1)") (class "Default")
      (node (ref "SW2") (pin "1") (pinfunction "1_1") (pintype "passive+no_connect"))
    )
    (net (code "44") (name "unconnected-(SW2-Pad4)") (class "Default")
      (node (ref "SW2") (pin "4") (pinfunction "4_4") (pintype "passive+no_connect"))
    )
    (net (code "45") (name "unconnected-(SW3-Pad1)") (class "Default")
      (node (ref "SW3") (pin "1") (pinfunction "1_1") (pintype "passive+no_connect"))
    )
    (net (code "46") (name "unconnected-(SW3-Pad4)") (class "Default")
      (node (ref "SW3") (pin "4") (pinfunction "4_4") (pintype "passive+no_connect"))
    )
    (net (code "47") (name "unconnected-(SW4-Pad1)") (class "Default")
      (node (ref "SW4") (pin "1") (pinfunction "1_1") (pintype "passive+no_connect"))
    )
    (net (code "48") (name "unconnected-(SW4-Pad4)") (class "Default")
      (node (ref "SW4") (pin "4") (pinfunction "4_4") (pintype "passive+no_connect"))
    )
    (net (code "49") (name "unconnected-(SW5-Pad1)") (class "Default")
      (node (ref "SW5") (pin "1") (pinfunction "1_1") (pintype "passive+no_connect"))
    )
    (net (code "50") (name "unconnected-(SW5-Pad4)") (class "Default")
      (node (ref "SW5") (pin "4") (pinfunction "4_4") (pintype "passive+no_connect"))
    )
    (net (code "51") (name "unconnected-(SW6-Pad1)") (class "Default")
      (node (ref "SW6") (pin "1") (pinfunction "1_1") (pintype "passive+no_connect"))
    )
    (net (code "52") (name "unconnected-(SW6-Pad4)") (class "Default")
      (node (ref "SW6") (pin "4") (pinfunction "4_4") (pintype "passive+no_connect"))
    )
    (net (code "53") (name "unconnected-(U1-ADC6-Pad19)") (class "Default")
      (node (ref "U1") (pin "19") (pinfunction "ADC6_19") (pintype "input+no_connect"))
    )
    (net (code "54") (name "unconnected-(U1-ADC7-Pad22)") (class "Default")
      (node (ref "U1") (pin "22") (pinfunction "ADC7_22") (pintype "input+no_connect"))
    )
    (net (code "55") (name "unconnected-(U1-PC1_(ADC1{slash}PCINT9)-Pad24)") (class "Default")
      (node (ref "U1") (pin "24") (pinfunction "PC1_(ADC1/PCINT9)_24") (pintype "bidirectional"))
    )
    (net (code "56") (name "unconnected-(U1-PC2_(ADC2{slash}PCINT10)-Pad25)") (class "Default")
      (node (ref "U1") (pin "25") (pinfunction "PC2_(ADC2/PCINT10)_25") (pintype "bidirectional"))
    )
    (net (code "57") (name "unconnected-(U1-PC3_(ADC3{slash}PCINT11)-Pad26)") (class "Default")
      (node (ref "U1") (pin "26") (pinfunction "PC3_(ADC3/PCINT11)_26") (pintype "bidirectional"))
    )
    (net (code "58") (name "unconnected-(U1-PD2_(INT0{slash}PCINT18)-Pad32)") (class "Default")
      (node (ref "U1") (pin "32") (pinfunction "PD2_(INT0/PCINT18)_32") (pintype "bidirectional"))
    )
    (net (code "59") (name "unconnected-(U1-PD3_(PCINT19{slash}OC2B{slash}INT1)-Pad1)") (class "Default")
      (node (ref "U1") (pin "1") (pinfunction "PD3_(PCINT19/OC2B/INT1)_1") (pintype "bidirectional"))
    )
    (net (code "60") (name "unconnected-(U1-PD4_(PCINT20{slash}XCK{slash}T0)-Pad2)") (class "Default")
      (node (ref "U1") (pin "2") (pinfunction "PD4_(PCINT20/XCK/T0)_2") (pintype "bidirectional"))
    )
    (net (code "61") (name "unconnected-(U3B-INB+-Pad5)") (class "Default")
      (node (ref "U3") (pin "5") (pinfunction "INB+_5") (pintype "input+no_connect"))
    )
    (net (code "62") (name "unconnected-(U3B-INB--Pad6)") (class "Default")
      (node (ref "U3") (pin "6") (pinfunction "INB-_6") (pintype "input+no_connect"))
    )
    (net (code "63") (name "unconnected-(U3B-OUTB-Pad7)") (class "Default")
      (node (ref "U3") (pin "7") (pinfunction "OUTB_7") (pintype "output+no_connect"))
    )
    (net (code "64") (name "unconnected-(U4-RS232-Pad15)") (class "Default")
      (node (ref "U4") (pin "15") (pinfunction "RS232_15") (pintype "input+no_connect"))
    )
    (net (code "65") (name "unconnected-(U4-~{CTS}-Pad9)") (class "Default")
      (node (ref "U4") (pin "9") (pinfunction "~{CTS}_9") (pintype "input+no_connect"))
    )
    (net (code "66") (name "unconnected-(U4-~{DCD}-Pad12)") (class "Default")
      (node (ref "U4") (pin "12") (pinfunction "~{DCD}_12") (pintype "input+no_connect"))
    )
    (net (code "67") (name "unconnected-(U4-~{DSR}-Pad10)") (class "Default")
      (node (ref "U4") (pin "10") (pinfunction "~{DSR}_10") (pintype "input+no_connect"))
    )
    (net (code "68") (name "unconnected-(U4-~{RI}-Pad11)") (class "Default")
      (node (ref "U4") (pin "11") (pinfunction "~{RI}_11") (pintype "input+no_connect"))
    )
    (net (code "69") (name "unconnected-(U4-~{RTS}-Pad14)") (class "Default")
      (node (ref "U4") (pin "14") (pinfunction "~{RTS}_14") (pintype "output+no_connect"))
    )
  )
)
